# MCU.net
KiCad netlist of a schematic drawn in Altium Designer
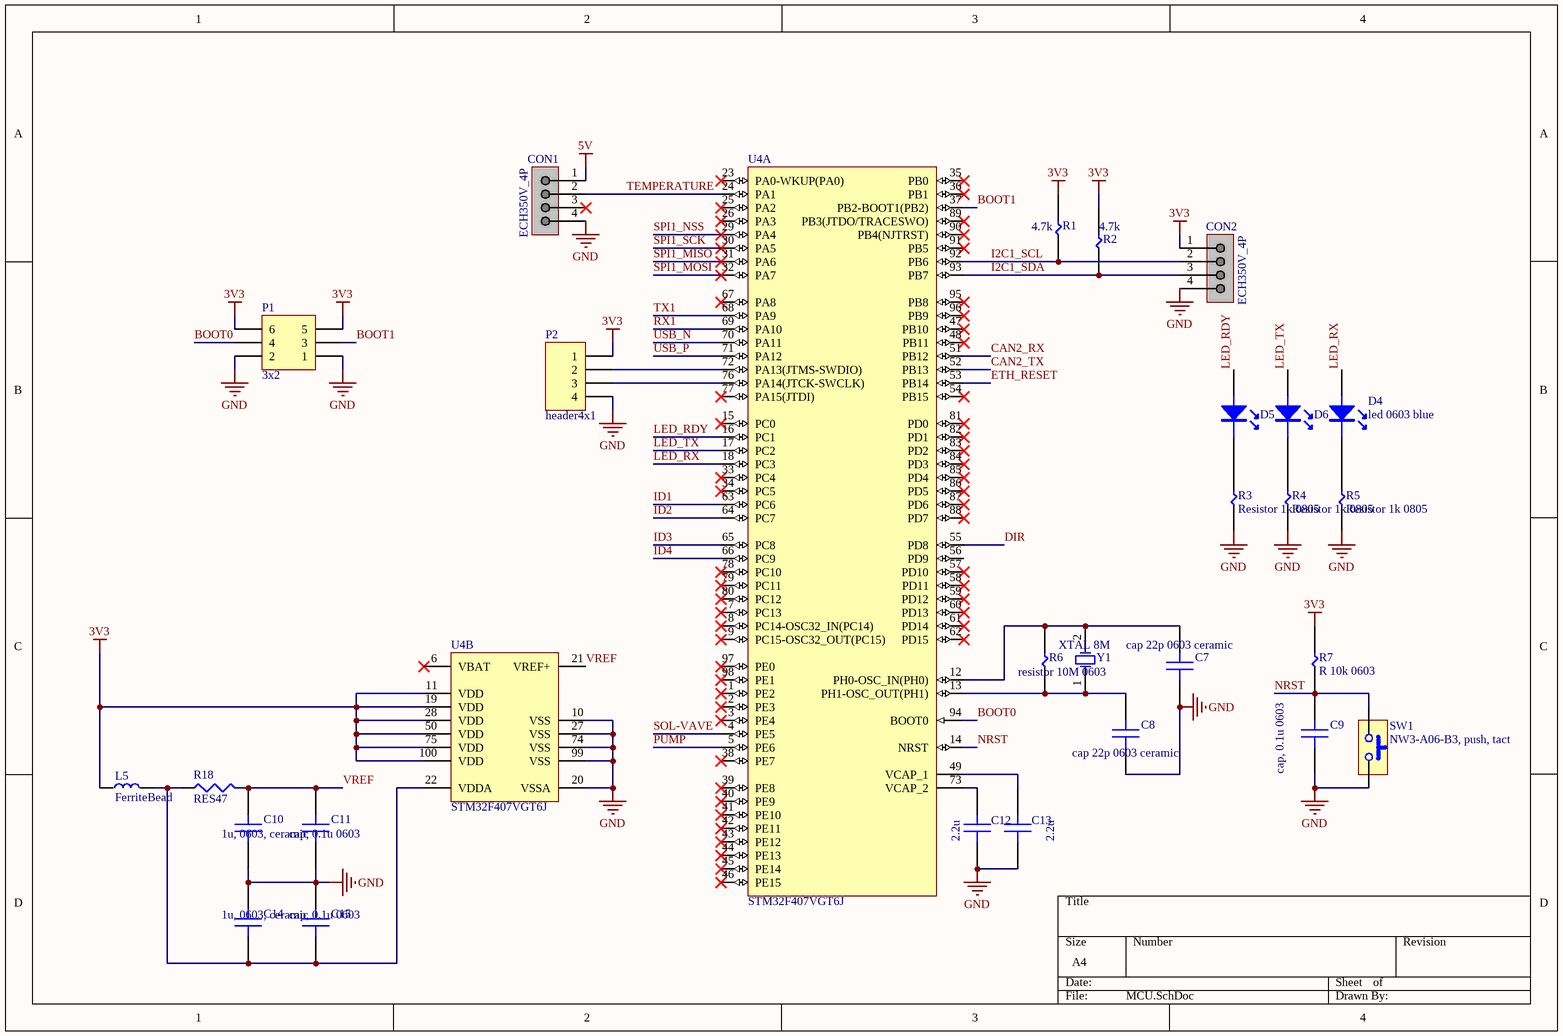
[diagram p0: MCU.SchDoc]

(export (version "E")
  (design (tool "Eeschema 10.0.6"))
  (components
    (comp (ref "C7")
      (value "cap 22p 0603 ceramic")
      (footprint "CAP22p_0603_ceramic")
      (libsource (lib "MyLIB240624") (part "CAP22p_0603_ceramic"))
    )
    (comp (ref "C8")
      (value "cap 22p 0603 ceramic")
      (footprint "CAP22p_0603_ceramic")
      (libsource (lib "MyLIB240624") (part "CAP22p_0603_ceramic"))
    )
    (comp (ref "C9")
      (value "cap, 0.1u 0603")
      (footprint "CAP0.1u_0603_ceramic")
      (libsource (lib "MyLIB240624") (part "CAP0.1u_0603_ceramic"))
    )
    (comp (ref "C10")
      (value "1u, 0603, ceramic")
      (footprint "CAP1u_0603_ceramic")
      (libsource (lib "MyLIB240624") (part "CAP1u_0603_ceramic"))
    )
    (comp (ref "C11")
      (value "cap, 0.1u 0603")
      (footprint "CAP0.1u_0603_ceramic")
      (libsource (lib "MyLIB240624") (part "CAP0.1u_0603_ceramic"))
    )
    (comp (ref "C12")
      (value "2.2u")
      (footprint "CAP2.2u_0603")
      (description "CAP2.2u_0603")
      (libsource (lib "SensoMonitor") (part "CAP2.2u_0603"))
    )
    (comp (ref "C13")
      (value "2.2u")
      (footprint "CAP2.2u_0603")
      (description "CAP2.2u_0603")
      (libsource (lib "SensoMonitor") (part "CAP2.2u_0603"))
    )
    (comp (ref "C14")
      (value "1u, 0603, ceramic")
      (footprint "CAP1u_0603_ceramic")
      (libsource (lib "MyLIB240624") (part "CAP1u_0603_ceramic"))
    )
    (comp (ref "C15")
      (value "cap, 0.1u 0603")
      (footprint "CAP0.1u_0603_ceramic")
      (libsource (lib "MyLIB240624") (part "CAP0.1u_0603_ceramic"))
    )
    (comp (ref "CON1")
      (value "ECH350V_4P")
      (footprint "CON4P_ECH350V")
      (description "Connector, Terminal block 4p_ECH350V")
      (libsource (lib "SensoMonitor") (part "CON4P_ECH350V"))
    )
    (comp (ref "CON2")
      (value "ECH350V_4P")
      (footprint "CON4P_ECH350V")
      (description "Connector, Terminal block 4p_ECH350V")
      (libsource (lib "") (part "CON4P_ECH350V_1"))
    )
    (comp (ref "D4")
      (value "led 0603 blue")
      (footprint "LED0603_BLUE")
      (libsource (lib "MyLIB240624") (part "LED0603_BLUE"))
    )
    (comp (ref "D5")
      (value "LED")
      (footprint "LED0603_GREEN")
      (libsource (lib "MyLIB240624") (part "LED0603_GREEN"))
    )
    (comp (ref "D6")
      (value "LED")
      (footprint "LED0603_GREEN")
      (libsource (lib "MyLIB240624") (part "LED0603_GREEN"))
    )
    (comp (ref "L5")
      (value "FerriteBead")
      (footprint "FerriteBD1608_102")
      (description "FCM1608KF-102T02, 200mA 1 700mΩ 1kΩ@100MHz ±25% 0603 Ferrite Beads ROHS")
      (fields
        (field (name "MANUFACTURER") "Tai Tech")
        (field (name "MANUFACTURER PART NUMBER") "FCM1608KF-102T02")
      )
      (libsource (lib "SensoMonitor") (part "FerriteBD1608_102"))
    )
    (comp (ref "P1")
      (value "3x2")
      (footprint "HDR3X2")
      (description "header 3x2")
      (libsource (lib "MyLIB240624") (part "HEADER3X2"))
    )
    (comp (ref "P2")
      (value "header4x1")
      (footprint "HEADER4X1")
      (libsource (lib "MyLIB240624") (part "HEADER4X1"))
    )
    (comp (ref "R1")
      (value "4.7k")
      (footprint "RES4.7k_0603")
      (libsource (lib "MyLIB240624") (part "RES4.7k_0603"))
    )
    (comp (ref "R2")
      (value "4.7k")
      (footprint "RES4.7k_0603")
      (libsource (lib "MyLIB240624") (part "RES4.7k_0603"))
    )
    (comp (ref "R3")
      (value "Resistor 1k 0805")
      (footprint "RES1K_0805")
      (description "resistor 1k 0805")
      (libsource (lib "MyLIB240624") (part "RES1K_0805"))
    )
    (comp (ref "R4")
      (value "Resistor 1k 0805")
      (footprint "RES1K_0805")
      (description "resistor 1k 0805")
      (libsource (lib "MyLIB240624") (part "RES1K_0805"))
    )
    (comp (ref "R5")
      (value "Resistor 1k 0805")
      (footprint "RES1K_0805")
      (description "resistor 1k 0805")
      (libsource (lib "MyLIB240624") (part "RES1K_0805"))
    )
    (comp (ref "R6")
      (value "resistor 10M 0603")
      (footprint "RES10M_0603")
      (libsource (lib "MyLIB240624") (part "RES10M_0603"))
    )
    (comp (ref "R7")
      (value "R 10k 0603")
      (footprint "RES10K_0603")
      (libsource (lib "MyLIB240624") (part "RES10K_0603"))
    )
    (comp (ref "R18")
      (value "RES47")
      (footprint "RES47_0603")
      (description "RES47_0603")
      (libsource (lib "SensoMonitor") (part "RES47_0603"))
    )
    (comp (ref "SW1")
      (value "NW3-A06-B3, push, tact")
      (footprint "SW_TACT1")
      (description "NW3-A06-B3")
      (libsource (lib "MyLIB240624") (part "SW_TACT1"))
    )
    (comp (ref "U4")
      (value "STM32F407VGT6J")
      (footprint "STM-LQFP100_L")
      (fields (field (name "MANUFACTURER") "STMicroelectronics"))
      (libsource (lib "Altium Content Vault") (part "MC-ARM-STM32F40X_41X-SQ100"))
    )
    (comp (ref "Y1")
      (value "XTAL 8M")
      (footprint "XTAL_SMD_8M")
      (libsource (lib "MyLIB240624") (part "XTAL8M"))
    )
  )
  (nets
    (net (code "1") (name "/BOOT0") (class "Default")
      (node (ref "P1") (pin "4") (pinfunction "4_4") (pintype "passive"))
      (node (ref "U4") (pin "94") (pinfunction "BOOT0_94") (pintype "input"))
    )
    (net (code "2") (name "/BOOT1") (class "Default")
      (node (ref "P1") (pin "3") (pinfunction "3_3") (pintype "passive"))
      (node (ref "U4") (pin "37") (pinfunction "PB2-BOOT1(PB2)_37") (pintype "bidirectional"))
    )
    (net (code "3") (name "/CAN2_RX") (class "Default")
      (node (ref "U4") (pin "51") (pinfunction "PB12_51") (pintype "bidirectional"))
    )
    (net (code "4") (name "/CAN2_TX") (class "Default")
      (node (ref "U4") (pin "52") (pinfunction "PB13_52") (pintype "bidirectional"))
    )
    (net (code "5") (name "/DIR") (class "Default")
      (node (ref "U4") (pin "55") (pinfunction "PD8_55") (pintype "bidirectional"))
    )
    (net (code "6") (name "/ETH_RESET") (class "Default")
      (node (ref "U4") (pin "53") (pinfunction "PB14_53") (pintype "bidirectional"))
    )
    (net (code "7") (name "/I2C1_SCL") (class "Default")
      (node (ref "CON2") (pin "2") (pinfunction "150_2") (pintype "passive"))
      (node (ref "R1") (pin "1") (pinfunction "1_1") (pintype "passive"))
      (node (ref "U4") (pin "92") (pinfunction "PB6_92") (pintype "bidirectional"))
    )
    (net (code "8") (name "/I2C1_SDA") (class "Default")
      (node (ref "CON2") (pin "3") (pinfunction "150_3") (pintype "passive"))
      (node (ref "R2") (pin "1") (pinfunction "1_1") (pintype "passive"))
      (node (ref "U4") (pin "93") (pinfunction "PB7_93") (pintype "bidirectional"))
    )
    (net (code "9") (name "/ID1") (class "Default")
      (node (ref "U4") (pin "63") (pinfunction "PC6_63") (pintype "bidirectional"))
    )
    (net (code "10") (name "/ID2") (class "Default")
      (node (ref "U4") (pin "64") (pinfunction "PC7_64") (pintype "bidirectional"))
    )
    (net (code "11") (name "/ID3") (class "Default")
      (node (ref "U4") (pin "65") (pinfunction "PC8_65") (pintype "bidirectional"))
    )
    (net (code "12") (name "/ID4") (class "Default")
      (node (ref "U4") (pin "66") (pinfunction "PC9_66") (pintype "bidirectional"))
    )
    (net (code "13") (name "/LED_RDY") (class "Default")
      (node (ref "D5") (pin "A") (pinfunction "1_A") (pintype "passive"))
      (node (ref "U4") (pin "16") (pinfunction "PC1_16") (pintype "bidirectional"))
    )
    (net (code "14") (name "/LED_RX") (class "Default")
      (node (ref "D4") (pin "A") (pinfunction "1_A") (pintype "passive"))
      (node (ref "U4") (pin "18") (pinfunction "PC3_18") (pintype "bidirectional"))
    )
    (net (code "15") (name "/LED_TX") (class "Default")
      (node (ref "D6") (pin "A") (pinfunction "1_A") (pintype "passive"))
      (node (ref "U4") (pin "17") (pinfunction "PC2_17") (pintype "bidirectional"))
    )
    (net (code "16") (name "/NRST") (class "Default")
      (node (ref "C9") (pin "2") (pinfunction "2_2") (pintype "passive"))
      (node (ref "R7") (pin "1") (pinfunction "1_1") (pintype "passive"))
      (node (ref "SW1") (pin "1") (pinfunction "1_1") (pintype "passive"))
      (node (ref "U4") (pin "14") (pinfunction "NRST_14") (pintype "bidirectional"))
    )
    (net (code "17") (name "/PUMP") (class "Default")
      (node (ref "U4") (pin "5") (pinfunction "PE6_5") (pintype "bidirectional"))
    )
    (net (code "18") (name "/RX1") (class "Default")
      (node (ref "U4") (pin "69") (pinfunction "PA10_69") (pintype "bidirectional"))
    )
    (net (code "19") (name "/SOL-VAVE") (class "Default")
      (node (ref "U4") (pin "4") (pinfunction "PE5_4") (pintype "bidirectional"))
    )
    (net (code "20") (name "/SPI1_MISO") (class "Default")
      (node (ref "U4") (pin "31") (pinfunction "PA6_31") (pintype "bidirectional+no_connect"))
    )
    (net (code "21") (name "/SPI1_MOSI") (class "Default")
      (node (ref "U4") (pin "32") (pinfunction "PA7_32") (pintype "bidirectional+no_connect"))
    )
    (net (code "22") (name "/SPI1_NSS") (class "Default")
      (node (ref "U4") (pin "29") (pinfunction "PA4_29") (pintype "bidirectional+no_connect"))
    )
    (net (code "23") (name "/SPI1_SCK") (class "Default")
      (node (ref "U4") (pin "30") (pinfunction "PA5_30") (pintype "bidirectional+no_connect"))
    )
    (net (code "24") (name "/TEMPERATURE") (class "Default")
      (node (ref "CON1") (pin "2") (pinfunction "150_2") (pintype "passive"))
      (node (ref "U4") (pin "24") (pinfunction "PA1_24") (pintype "bidirectional"))
    )
    (net (code "25") (name "/TX1") (class "Default")
      (node (ref "U4") (pin "68") (pinfunction "PA9_68") (pintype "bidirectional"))
    )
    (net (code "26") (name "/USB_N") (class "Default")
      (node (ref "U4") (pin "70") (pinfunction "PA11_70") (pintype "bidirectional"))
    )
    (net (code "27") (name "/USB_P") (class "Default")
      (node (ref "U4") (pin "71") (pinfunction "PA12_71") (pintype "bidirectional"))
    )
    (net (code "28") (name "/VREF") (class "Default")
      (node (ref "C10") (pin "2") (pinfunction "2_2") (pintype "passive"))
      (node (ref "C11") (pin "2") (pinfunction "2_2") (pintype "passive"))
      (node (ref "R18") (pin "2") (pinfunction "2_2") (pintype "passive"))
      (node (ref "U4") (pin "21") (pinfunction "VREF+_21") (pintype "power_in"))
    )
    (net (code "29") (name "3V3") (class "Default")
      (node (ref "CON2") (pin "1") (pinfunction "150_1") (pintype "passive"))
      (node (ref "L5") (pin "1") (pinfunction "1_1") (pintype "passive"))
      (node (ref "P1") (pin "5") (pinfunction "5_5") (pintype "passive"))
      (node (ref "P1") (pin "6") (pinfunction "6_6") (pintype "passive"))
      (node (ref "P2") (pin "1") (pinfunction "1_1") (pintype "passive"))
      (node (ref "R1") (pin "2") (pinfunction "2_2") (pintype "passive"))
      (node (ref "R2") (pin "2") (pinfunction "2_2") (pintype "passive"))
      (node (ref "R7") (pin "2") (pinfunction "2_2") (pintype "passive"))
      (node (ref "U4") (pin "100") (pinfunction "VDD_100") (pintype "power_in"))
      (node (ref "U4") (pin "11") (pinfunction "VDD_11") (pintype "power_in"))
      (node (ref "U4") (pin "19") (pinfunction "VDD_19") (pintype "power_in"))
      (node (ref "U4") (pin "28") (pinfunction "VDD_28") (pintype "power_in"))
      (node (ref "U4") (pin "50") (pinfunction "VDD_50") (pintype "power_in"))
      (node (ref "U4") (pin "75") (pinfunction "VDD_75") (pintype "power_in"))
    )
    (net (code "30") (name "5V") (class "Default")
      (node (ref "CON1") (pin "1") (pinfunction "150_1") (pintype "passive"))
    )
    (net (code "31") (name "GND") (class "Default")
      (node (ref "C10") (pin "1") (pinfunction "1_1") (pintype "passive"))
      (node (ref "C11") (pin "1") (pinfunction "1_1") (pintype "passive"))
      (node (ref "C12") (pin "1") (pinfunction "1_1") (pintype "passive"))
      (node (ref "C13") (pin "1") (pinfunction "1_1") (pintype "passive"))
      (node (ref "C14") (pin "2") (pinfunction "2_2") (pintype "passive"))
      (node (ref "C15") (pin "2") (pinfunction "2_2") (pintype "passive"))
      (node (ref "C7") (pin "1") (pinfunction "1_1") (pintype "passive"))
      (node (ref "C8") (pin "1") (pinfunction "1_1") (pintype "passive"))
      (node (ref "C9") (pin "1") (pinfunction "1_1") (pintype "passive"))
      (node (ref "CON1") (pin "4") (pinfunction "150_4") (pintype "passive"))
      (node (ref "CON2") (pin "4") (pinfunction "150_4") (pintype "passive"))
      (node (ref "P1") (pin "1") (pinfunction "1_1") (pintype "passive"))
      (node (ref "P1") (pin "2") (pinfunction "2_2") (pintype "passive"))
      (node (ref "P2") (pin "4") (pinfunction "4_4") (pintype "passive"))
      (node (ref "R3") (pin "1") (pinfunction "1_1") (pintype "passive"))
      (node (ref "R4") (pin "1") (pinfunction "1_1") (pintype "passive"))
      (node (ref "R5") (pin "1") (pinfunction "1_1") (pintype "passive"))
      (node (ref "SW1") (pin "2") (pinfunction "2_2") (pintype "passive"))
      (node (ref "U4") (pin "10") (pinfunction "VSS_10") (pintype "power_in"))
      (node (ref "U4") (pin "20") (pinfunction "VSSA_20") (pintype "power_in"))
      (node (ref "U4") (pin "27") (pinfunction "VSS_27") (pintype "power_in"))
      (node (ref "U4") (pin "74") (pinfunction "VSS_74") (pintype "power_in"))
      (node (ref "U4") (pin "99") (pinfunction "VSS_99") (pintype "power_in"))
    )
    (net (code "32") (name "Net-(D4-2)") (class "Default")
      (node (ref "D4") (pin "K") (pinfunction "2_K") (pintype "passive"))
      (node (ref "R5") (pin "2") (pinfunction "2_2") (pintype "passive"))
    )
    (net (code "33") (name "Net-(D5-2)") (class "Default")
      (node (ref "D5") (pin "K") (pinfunction "2_K") (pintype "passive"))
      (node (ref "R3") (pin "2") (pinfunction "2_2") (pintype "passive"))
    )
    (net (code "34") (name "Net-(D6-2)") (class "Default")
      (node (ref "D6") (pin "K") (pinfunction "2_K") (pintype "passive"))
      (node (ref "R4") (pin "2") (pinfunction "2_2") (pintype "passive"))
    )
    (net (code "35") (name "Net-(U4A-PA13(JTMS-SWDIO))") (class "Default")
      (node (ref "P2") (pin "2") (pinfunction "2_2") (pintype "passive"))
      (node (ref "U4") (pin "72") (pinfunction "PA13(JTMS-SWDIO)_72") (pintype "bidirectional"))
    )
    (net (code "36") (name "Net-(U4A-PA14(JTCK-SWCLK))") (class "Default")
      (node (ref "P2") (pin "3") (pinfunction "3_3") (pintype "passive"))
      (node (ref "U4") (pin "76") (pinfunction "PA14(JTCK-SWCLK)_76") (pintype "bidirectional"))
    )
    (net (code "37") (name "Net-(U4A-PH0-OSC_IN(PH0))") (class "Default")
      (node (ref "C7") (pin "2") (pinfunction "2_2") (pintype "passive"))
      (node (ref "R6") (pin "2") (pinfunction "2_2") (pintype "passive"))
      (node (ref "U4") (pin "12") (pinfunction "PH0-OSC_IN(PH0)_12") (pintype "bidirectional"))
      (node (ref "Y1") (pin "2") (pinfunction "OSC2_2") (pintype "passive"))
    )
    (net (code "38") (name "Net-(U4A-PH1-OSC_OUT(PH1))") (class "Default")
      (node (ref "C8") (pin "2") (pinfunction "2_2") (pintype "passive"))
      (node (ref "R6") (pin "1") (pinfunction "1_1") (pintype "passive"))
      (node (ref "U4") (pin "13") (pinfunction "PH1-OSC_OUT(PH1)_13") (pintype "bidirectional"))
      (node (ref "Y1") (pin "1") (pinfunction "OSC1_1") (pintype "passive"))
    )
    (net (code "39") (name "Net-(U4A-VCAP_1)") (class "Default")
      (node (ref "C13") (pin "2") (pinfunction "2_2") (pintype "passive"))
      (node (ref "U4") (pin "49") (pinfunction "VCAP_1_49") (pintype "power_in"))
    )
    (net (code "40") (name "Net-(U4A-VCAP_2)") (class "Default")
      (node (ref "C12") (pin "2") (pinfunction "2_2") (pintype "passive"))
      (node (ref "U4") (pin "73") (pinfunction "VCAP_2_73") (pintype "power_in"))
    )
    (net (code "41") (name "Net-(U4B-VDDA)") (class "Default")
      (node (ref "C14") (pin "1") (pinfunction "1_1") (pintype "passive"))
      (node (ref "C15") (pin "1") (pinfunction "1_1") (pintype "passive"))
      (node (ref "L5") (pin "2") (pinfunction "2_2") (pintype "passive"))
      (node (ref "R18") (pin "1") (pinfunction "1_1") (pintype "passive"))
      (node (ref "U4") (pin "22") (pinfunction "VDDA_22") (pintype "power_in"))
    )
    (net (code "42") (name "unconnected-(CON1-150-Pad3)") (class "Default")
      (node (ref "CON1") (pin "3") (pinfunction "150_3") (pintype "passive+no_connect"))
    )
    (net (code "43") (name "unconnected-(U4A-PA0-WKUP(PA0)-Pad23)") (class "Default")
      (node (ref "U4") (pin "23") (pinfunction "PA0-WKUP(PA0)_23") (pintype "bidirectional+no_connect"))
    )
    (net (code "44") (name "unconnected-(U4A-PA2-Pad25)") (class "Default")
      (node (ref "U4") (pin "25") (pinfunction "PA2_25") (pintype "bidirectional+no_connect"))
    )
    (net (code "45") (name "unconnected-(U4A-PA3-Pad26)") (class "Default")
      (node (ref "U4") (pin "26") (pinfunction "PA3_26") (pintype "bidirectional+no_connect"))
    )
    (net (code "46") (name "unconnected-(U4A-PA8-Pad67)") (class "Default")
      (node (ref "U4") (pin "67") (pinfunction "PA8_67") (pintype "bidirectional+no_connect"))
    )
    (net (code "47") (name "unconnected-(U4A-PA15(JTDI)-Pad77)") (class "Default")
      (node (ref "U4") (pin "77") (pinfunction "PA15(JTDI)_77") (pintype "bidirectional+no_connect"))
    )
    (net (code "48") (name "unconnected-(U4A-PB0-Pad35)") (class "Default")
      (node (ref "U4") (pin "35") (pinfunction "PB0_35") (pintype "bidirectional+no_connect"))
    )
    (net (code "49") (name "unconnected-(U4A-PB1-Pad36)") (class "Default")
      (node (ref "U4") (pin "36") (pinfunction "PB1_36") (pintype "bidirectional+no_connect"))
    )
    (net (code "50") (name "unconnected-(U4A-PB3(JTDO{slash}TRACESWO)-Pad89)") (class "Default")
      (node (ref "U4") (pin "89") (pinfunction "PB3(JTDO/TRACESWO)_89") (pintype "bidirectional+no_connect"))
    )
    (net (code "51") (name "unconnected-(U4A-PB4(NJTRST)-Pad90)") (class "Default")
      (node (ref "U4") (pin "90") (pinfunction "PB4(NJTRST)_90") (pintype "bidirectional+no_connect"))
    )
    (net (code "52") (name "unconnected-(U4A-PB5-Pad91)") (class "Default")
      (node (ref "U4") (pin "91") (pinfunction "PB5_91") (pintype "bidirectional+no_connect"))
    )
    (net (code "53") (name "unconnected-(U4A-PB8-Pad95)") (class "Default")
      (node (ref "U4") (pin "95") (pinfunction "PB8_95") (pintype "bidirectional+no_connect"))
    )
    (net (code "54") (name "unconnected-(U4A-PB9-Pad96)") (class "Default")
      (node (ref "U4") (pin "96") (pinfunction "PB9_96") (pintype "bidirectional+no_connect"))
    )
    (net (code "55") (name "unconnected-(U4A-PB10-Pad47)") (class "Default")
      (node (ref "U4") (pin "47") (pinfunction "PB10_47") (pintype "bidirectional+no_connect"))
    )
    (net (code "56") (name "unconnected-(U4A-PB11-Pad48)") (class "Default")
      (node (ref "U4") (pin "48") (pinfunction "PB11_48") (pintype "bidirectional+no_connect"))
    )
    (net (code "57") (name "unconnected-(U4A-PB15-Pad54)") (class "Default")
      (node (ref "U4") (pin "54") (pinfunction "PB15_54") (pintype "bidirectional+no_connect"))
    )
    (net (code "58") (name "unconnected-(U4A-PC0-Pad15)") (class "Default")
      (node (ref "U4") (pin "15") (pinfunction "PC0_15") (pintype "bidirectional+no_connect"))
    )
    (net (code "59") (name "unconnected-(U4A-PC4-Pad33)") (class "Default")
      (node (ref "U4") (pin "33") (pinfunction "PC4_33") (pintype "bidirectional+no_connect"))
    )
    (net (code "60") (name "unconnected-(U4A-PC5-Pad34)") (class "Default")
      (node (ref "U4") (pin "34") (pinfunction "PC5_34") (pintype "bidirectional+no_connect"))
    )
    (net (code "61") (name "unconnected-(U4A-PC10-Pad78)") (class "Default")
      (node (ref "U4") (pin "78") (pinfunction "PC10_78") (pintype "bidirectional+no_connect"))
    )
    (net (code "62") (name "unconnected-(U4A-PC11-Pad79)") (class "Default")
      (node (ref "U4") (pin "79") (pinfunction "PC11_79") (pintype "bidirectional+no_connect"))
    )
    (net (code "63") (name "unconnected-(U4A-PC12-Pad80)") (class "Default")
      (node (ref "U4") (pin "80") (pinfunction "PC12_80") (pintype "bidirectional+no_connect"))
    )
    (net (code "64") (name "unconnected-(U4A-PC13-Pad7)") (class "Default")
      (node (ref "U4") (pin "7") (pinfunction "PC13_7") (pintype "bidirectional+no_connect"))
    )
    (net (code "65") (name "unconnected-(U4A-PC14-OSC32_IN(PC14)-Pad8)") (class "Default")
      (node (ref "U4") (pin "8") (pinfunction "PC14-OSC32_IN(PC14)_8") (pintype "bidirectional+no_connect"))
    )
    (net (code "66") (name "unconnected-(U4A-PC15-OSC32_OUT(PC15)-Pad9)") (class "Default")
      (node (ref "U4") (pin "9") (pinfunction "PC15-OSC32_OUT(PC15)_9") (pintype "bidirectional+no_connect"))
    )
    (net (code "67") (name "unconnected-(U4A-PD0-Pad81)") (class "Default")
      (node (ref "U4") (pin "81") (pinfunction "PD0_81") (pintype "bidirectional+no_connect"))
    )
    (net (code "68") (name "unconnected-(U4A-PD1-Pad82)") (class "Default")
      (node (ref "U4") (pin "82") (pinfunction "PD1_82") (pintype "bidirectional+no_connect"))
    )
    (net (code "69") (name "unconnected-(U4A-PD2-Pad83)") (class "Default")
      (node (ref "U4") (pin "83") (pinfunction "PD2_83") (pintype "bidirectional+no_connect"))
    )
    (net (code "70") (name "unconnected-(U4A-PD3-Pad84)") (class "Default")
      (node (ref "U4") (pin "84") (pinfunction "PD3_84") (pintype "bidirectional+no_connect"))
    )
    (net (code "71") (name "unconnected-(U4A-PD4-Pad85)") (class "Default")
      (node (ref "U4") (pin "85") (pinfunction "PD4_85") (pintype "bidirectional+no_connect"))
    )
    (net (code "72") (name "unconnected-(U4A-PD5-Pad86)") (class "Default")
      (node (ref "U4") (pin "86") (pinfunction "PD5_86") (pintype "bidirectional+no_connect"))
    )
    (net (code "73") (name "unconnected-(U4A-PD6-Pad87)") (class "Default")
      (node (ref "U4") (pin "87") (pinfunction "PD6_87") (pintype "bidirectional+no_connect"))
    )
    (net (code "74") (name "unconnected-(U4A-PD7-Pad88)") (class "Default")
      (node (ref "U4") (pin "88") (pinfunction "PD7_88") (pintype "bidirectional+no_connect"))
    )
    (net (code "75") (name "unconnected-(U4A-PD9-Pad56)") (class "Default")
      (node (ref "U4") (pin "56") (pinfunction "PD9_56") (pintype "bidirectional"))
    )
    (net (code "76") (name "unconnected-(U4A-PD10-Pad57)") (class "Default")
      (node (ref "U4") (pin "57") (pinfunction "PD10_57") (pintype "bidirectional+no_connect"))
    )
    (net (code "77") (name "unconnected-(U4A-PD11-Pad58)") (class "Default")
      (node (ref "U4") (pin "58") (pinfunction "PD11_58") (pintype "bidirectional+no_connect"))
    )
    (net (code "78") (name "unconnected-(U4A-PD12-Pad59)") (class "Default")
      (node (ref "U4") (pin "59") (pinfunction "PD12_59") (pintype "bidirectional+no_connect"))
    )
    (net (code "79") (name "unconnected-(U4A-PD13-Pad60)") (class "Default")
      (node (ref "U4") (pin "60") (pinfunction "PD13_60") (pintype "bidirectional+no_connect"))
    )
    (net (code "80") (name "unconnected-(U4A-PD14-Pad61)") (class "Default")
      (node (ref "U4") (pin "61") (pinfunction "PD14_61") (pintype "bidirectional+no_connect"))
    )
    (net (code "81") (name "unconnected-(U4A-PD15-Pad62)") (class "Default")
      (node (ref "U4") (pin "62") (pinfunction "PD15_62") (pintype "bidirectional+no_connect"))
    )
    (net (code "82") (name "unconnected-(U4A-PE0-Pad97)") (class "Default")
      (node (ref "U4") (pin "97") (pinfunction "PE0_97") (pintype "bidirectional+no_connect"))
    )
    (net (code "83") (name "unconnected-(U4A-PE1-Pad98)") (class "Default")
      (node (ref "U4") (pin "98") (pinfunction "PE1_98") (pintype "bidirectional+no_connect"))
    )
    (net (code "84") (name "unconnected-(U4A-PE2-Pad1)") (class "Default")
      (node (ref "U4") (pin "1") (pinfunction "PE2_1") (pintype "bidirectional+no_connect"))
    )
    (net (code "85") (name "unconnected-(U4A-PE3-Pad2)") (class "Default")
      (node (ref "U4") (pin "2") (pinfunction "PE3_2") (pintype "bidirectional+no_connect"))
    )
    (net (code "86") (name "unconnected-(U4A-PE4-Pad3)") (class "Default")
      (node (ref "U4") (pin "3") (pinfunction "PE4_3") (pintype "bidirectional+no_connect"))
    )
    (net (code "87") (name "unconnected-(U4A-PE7-Pad38)") (class "Default")
      (node (ref "U4") (pin "38") (pinfunction "PE7_38") (pintype "bidirectional+no_connect"))
    )
    (net (code "88") (name "unconnected-(U4A-PE8-Pad39)") (class "Default")
      (node (ref "U4") (pin "39") (pinfunction "PE8_39") (pintype "bidirectional+no_connect"))
    )
    (net (code "89") (name "unconnected-(U4A-PE9-Pad40)") (class "Default")
      (node (ref "U4") (pin "40") (pinfunction "PE9_40") (pintype "bidirectional+no_connect"))
    )
    (net (code "90") (name "unconnected-(U4A-PE10-Pad41)") (class "Default")
      (node (ref "U4") (pin "41") (pinfunction "PE10_41") (pintype "bidirectional+no_connect"))
    )
    (net (code "91") (name "unconnected-(U4A-PE11-Pad42)") (class "Default")
      (node (ref "U4") (pin "42") (pinfunction "PE11_42") (pintype "bidirectional+no_connect"))
    )
    (net (code "92") (name "unconnected-(U4A-PE12-Pad43)") (class "Default")
      (node (ref "U4") (pin "43") (pinfunction "PE12_43") (pintype "bidirectional+no_connect"))
    )
    (net (code "93") (name "unconnected-(U4A-PE13-Pad44)") (class "Default")
      (node (ref "U4") (pin "44") (pinfunction "PE13_44") (pintype "bidirectional+no_connect"))
    )
    (net (code "94") (name "unconnected-(U4A-PE14-Pad45)") (class "Default")
      (node (ref "U4") (pin "45") (pinfunction "PE14_45") (pintype "bidirectional+no_connect"))
    )
    (net (code "95") (name "unconnected-(U4A-PE15-Pad46)") (class "Default")
      (node (ref "U4") (pin "46") (pinfunction "PE15_46") (pintype "bidirectional+no_connect"))
    )
    (net (code "96") (name "unconnected-(U4B-VBAT-Pad6)") (class "Default")
      (node (ref "U4") (pin "6") (pinfunction "VBAT_6") (pintype "power_in+no_connect"))
    )
  )
)
